# SCH_Proj_2026_2026-04-17.net
KiCad netlist of a schematic drawn in EasyEDA
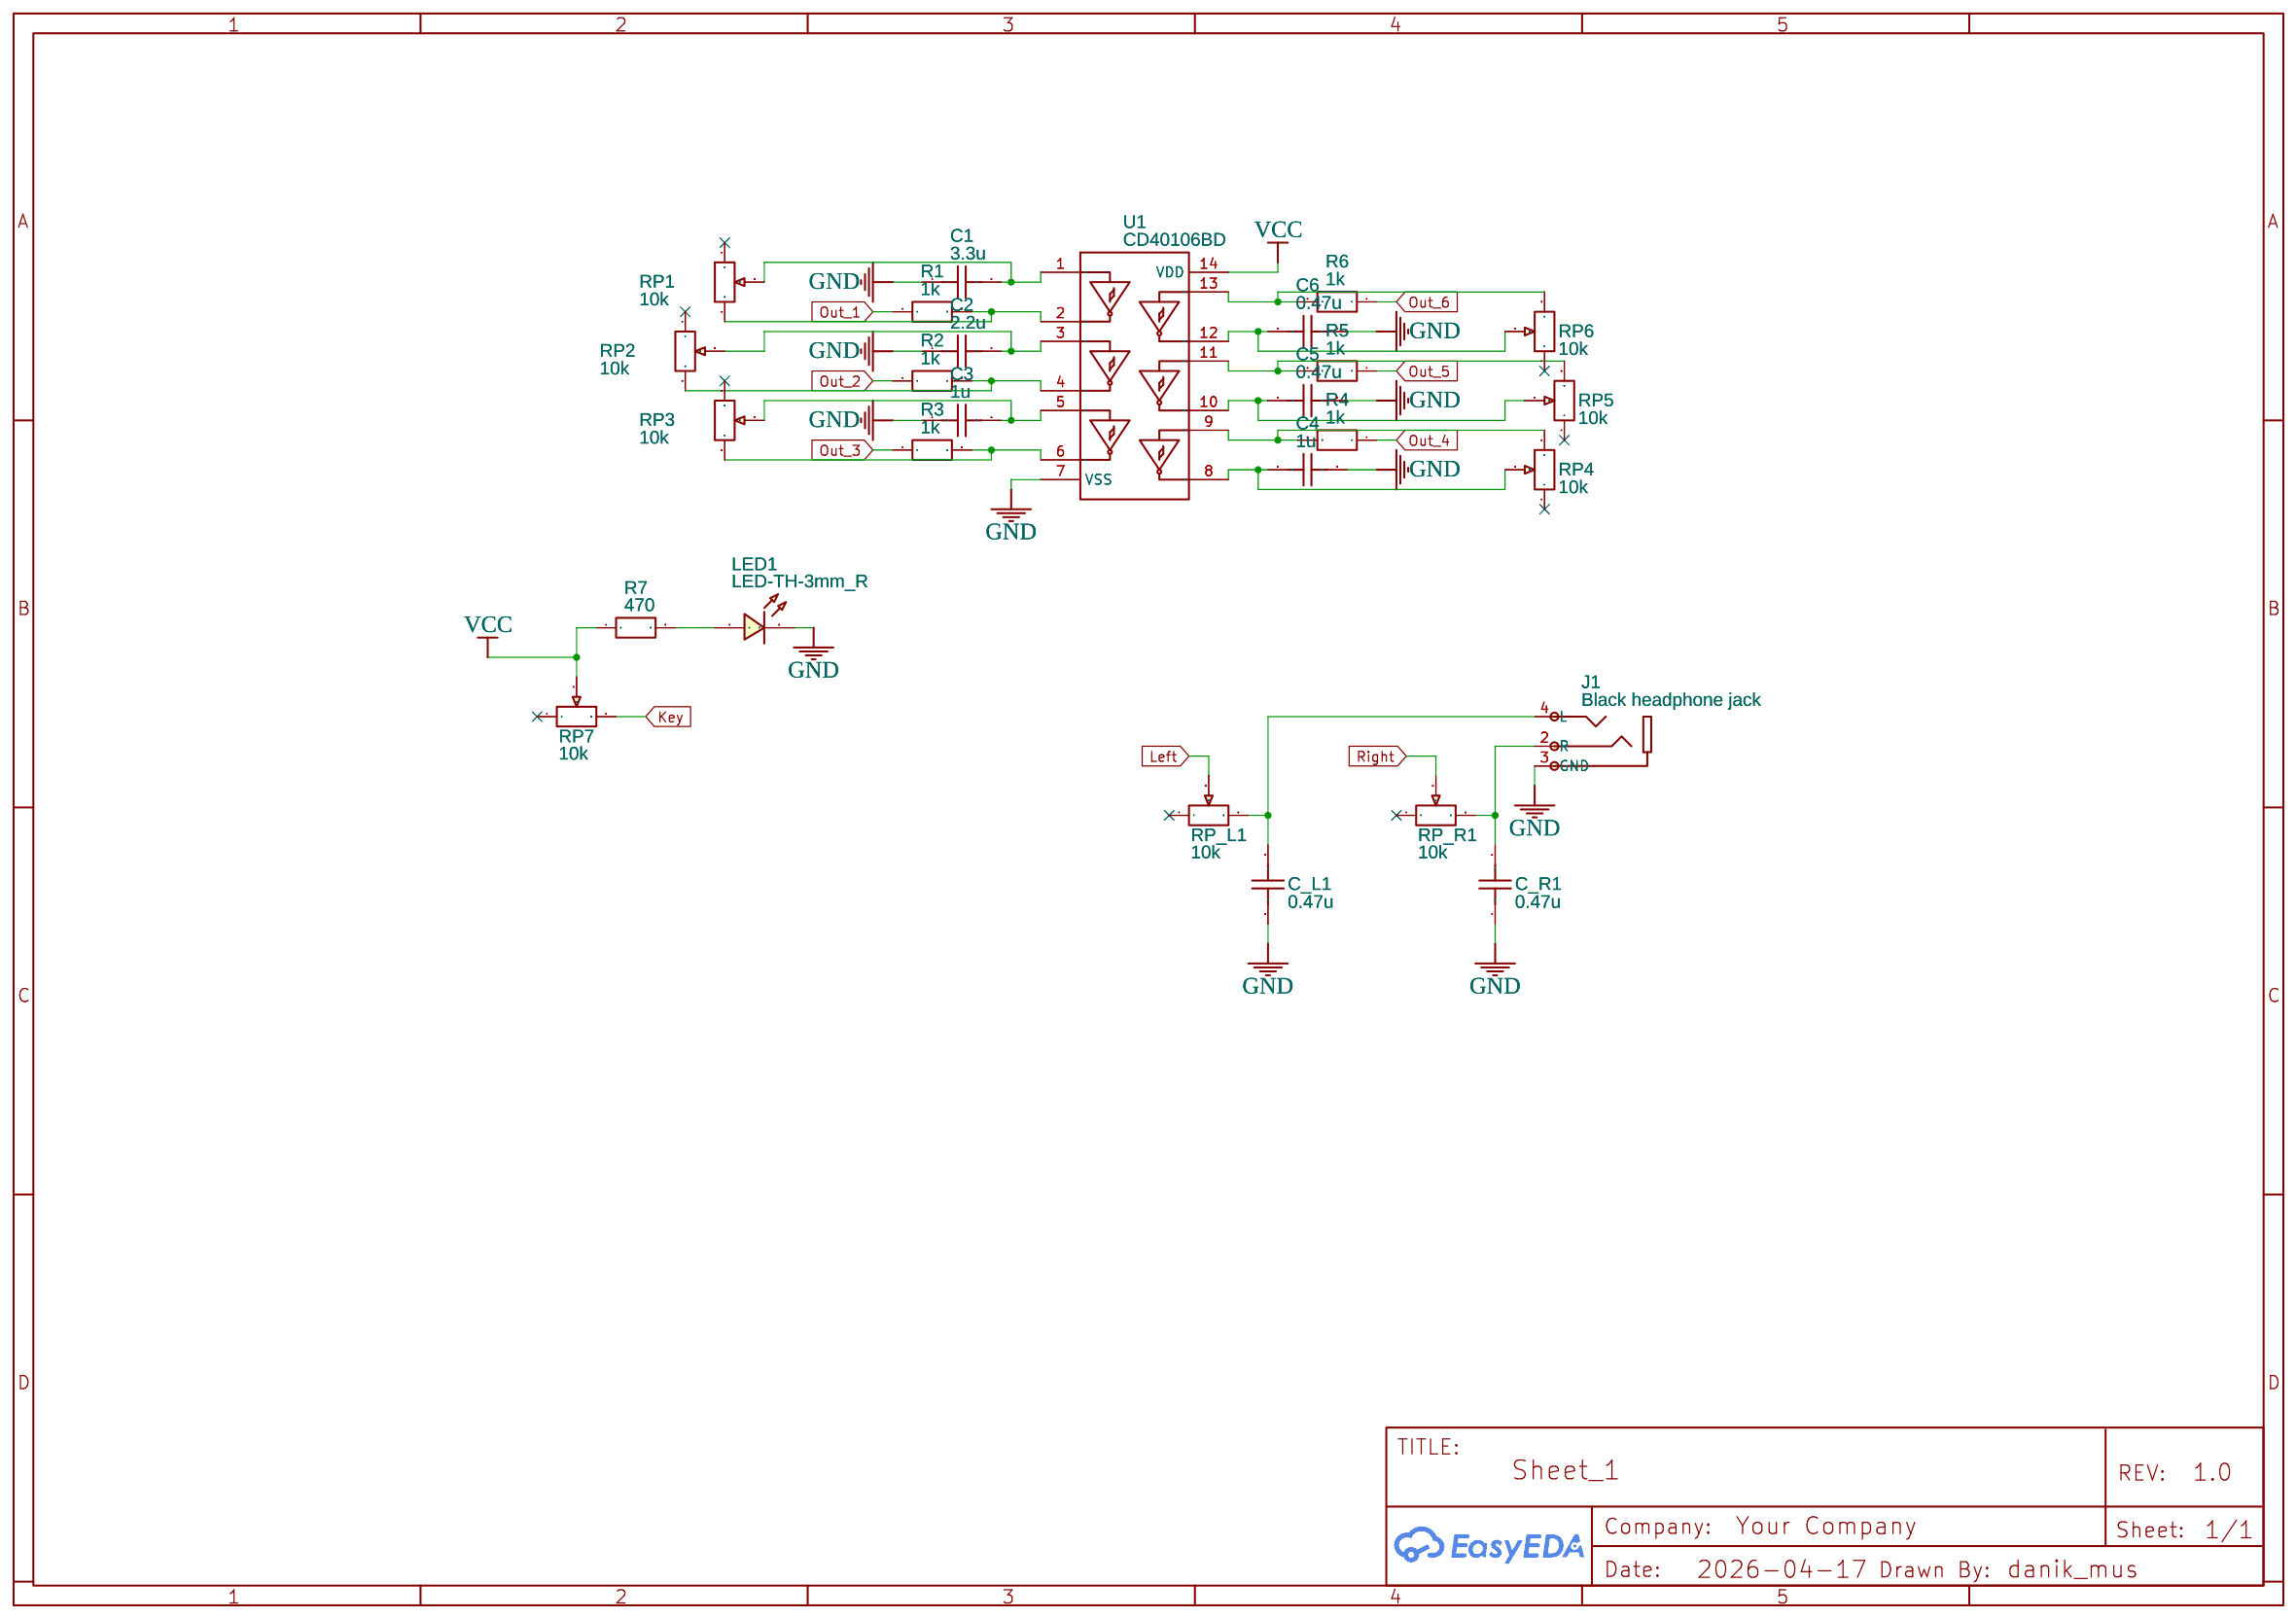
[diagram p0: schematic sheet]

(export (version "E")
  (design (tool "Eeschema 10.0.6"))
  (components
    (comp (ref "C1") (value "3.3u") (libsource (lib "") (part "C_0603_US_2")))
    (comp (ref "C2") (value "2.2u") (libsource (lib "") (part "C_0603_US_2")))
    (comp (ref "C3") (value "1u") (libsource (lib "") (part "C_0603_US_2")))
    (comp (ref "C4") (value "1u") (libsource (lib "") (part "C_0603_US")))
    (comp (ref "C5") (value "0.47u") (libsource (lib "") (part "C_0603_US")))
    (comp (ref "C6") (value "0.47u") (libsource (lib "") (part "C_0603_US")))
    (comp (ref "C_L1") (value "0.47u") (libsource (lib "") (part "C_0603_US_3")))
    (comp (ref "C_R1") (value "0.47u") (libsource (lib "") (part "C_0603_US_1")))
    (comp (ref "J1")
      (value "Black headphone jack")
      (fields (field (name "Manufacturer Part") "320B直插") (field (name "Manufacturer") "BOOMELE(博穆精密)"))
      (libsource (lib "") (part "Black headphone jack"))
    )
    (comp (ref "LED1")
      (value "LED-TH-3mm_R")
      (fields
        (field (name "Manufacturer Part") "204-10SDRD/S530-A3-L")
        (field (name "Manufacturer") "EVERLIGHT(台湾亿光)")
      )
      (libsource (lib "") (part "LED-TH-3mm_R"))
    )
    (comp (ref "R1") (value "1k") (libsource (lib "") (part "R_AXIAL-1.0_EU")))
    (comp (ref "R2") (value "1k") (libsource (lib "") (part "R_AXIAL-1.0_EU")))
    (comp (ref "R3") (value "1k") (libsource (lib "") (part "R_AXIAL-1.0_EU")))
    (comp (ref "R4") (value "1k") (libsource (lib "") (part "R_AXIAL-1.0_EU_1")))
    (comp (ref "R5") (value "1k") (libsource (lib "") (part "R_AXIAL-1.0_EU_1")))
    (comp (ref "R6") (value "1k") (libsource (lib "") (part "R_AXIAL-1.0_EU_1")))
    (comp (ref "R7") (value "470") (libsource (lib "") (part "R_AXIAL-1.0_EU")))
    (comp (ref "RP1") (value "10k") (libsource (lib "") (part "POTRES COPY COPY_2")))
    (comp (ref "RP2") (value "10k") (libsource (lib "") (part "POTRES COPY COPY_2")))
    (comp (ref "RP3") (value "10k") (libsource (lib "") (part "POTRES COPY COPY_2")))
    (comp (ref "RP4") (value "10k") (libsource (lib "") (part "POTRES COPY COPY_3")))
    (comp (ref "RP5") (value "10k") (libsource (lib "") (part "POTRES COPY COPY_3")))
    (comp (ref "RP6") (value "10k") (libsource (lib "") (part "POTRES COPY COPY_3")))
    (comp (ref "RP7") (value "10k") (libsource (lib "") (part "POTRES COPY COPY_4")))
    (comp (ref "RP_L1") (value "10k") (libsource (lib "") (part "POTRES COPY COPY_1")))
    (comp (ref "RP_R1") (value "10k") (libsource (lib "") (part "POTRES COPY COPY")))
    (comp (ref "U1")
      (value "CD40106BD")
      (fields (field (name "Manufacturer") "Sungine(双竞集成)"))
      (libsource (lib "") (part "CD40106BD"))
    )
  )
  (nets
    (net (code "1") (name "GND") (class "Default")
      (node (ref "C1") (pin "1") (pinfunction "1_1") (pintype "unspecified"))
      (node (ref "C2") (pin "1") (pinfunction "1_1") (pintype "unspecified"))
      (node (ref "C3") (pin "1") (pinfunction "1_1") (pintype "unspecified"))
      (node (ref "C4") (pin "1") (pinfunction "1_1") (pintype "unspecified"))
      (node (ref "C5") (pin "1") (pinfunction "1_1") (pintype "unspecified"))
      (node (ref "C6") (pin "1") (pinfunction "1_1") (pintype "unspecified"))
      (node (ref "C_L1") (pin "1") (pinfunction "1_1") (pintype "unspecified"))
      (node (ref "C_R1") (pin "1") (pinfunction "1_1") (pintype "unspecified"))
      (node (ref "J1") (pin "3") (pinfunction "GND_3") (pintype "input"))
      (node (ref "LED1") (pin "2") (pinfunction "2_2") (pintype "unspecified"))
      (node (ref "U1") (pin "7") (pinfunction "VSS_7") (pintype "unspecified"))
    )
    (net (code "2") (name "Key") (class "Default")
      (node (ref "RP7") (pin "3") (pinfunction "3_3") (pintype "input"))
    )
    (net (code "3") (name "Left") (class "Default")
      (node (ref "RP_L1") (pin "2") (pinfunction "2_2") (pintype "input"))
    )
    (net (code "4") (name "Net-(C1-Pad2)") (class "Default")
      (node (ref "C1") (pin "2") (pinfunction "2_2") (pintype "unspecified"))
      (node (ref "RP1") (pin "2") (pinfunction "2_2") (pintype "input"))
      (node (ref "U1") (pin "1") (pinfunction "1_1") (pintype "unspecified"))
    )
    (net (code "5") (name "Net-(C2-Pad2)") (class "Default")
      (node (ref "C2") (pin "2") (pinfunction "2_2") (pintype "unspecified"))
      (node (ref "RP2") (pin "2") (pinfunction "2_2") (pintype "input"))
      (node (ref "U1") (pin "3") (pinfunction "3_3") (pintype "unspecified"))
    )
    (net (code "6") (name "Net-(C3-Pad2)") (class "Default")
      (node (ref "C3") (pin "2") (pinfunction "2_2") (pintype "unspecified"))
      (node (ref "RP3") (pin "2") (pinfunction "2_2") (pintype "input"))
      (node (ref "U1") (pin "5") (pinfunction "5_5") (pintype "unspecified"))
    )
    (net (code "7") (name "Net-(C4-Pad2)") (class "Default")
      (node (ref "C4") (pin "2") (pinfunction "2_2") (pintype "unspecified"))
      (node (ref "RP4") (pin "2") (pinfunction "2_2") (pintype "input"))
      (node (ref "U1") (pin "8") (pinfunction "8_8") (pintype "unspecified"))
    )
    (net (code "8") (name "Net-(C5-Pad2)") (class "Default")
      (node (ref "C5") (pin "2") (pinfunction "2_2") (pintype "unspecified"))
      (node (ref "RP5") (pin "2") (pinfunction "2_2") (pintype "input"))
      (node (ref "U1") (pin "10") (pinfunction "10_10") (pintype "unspecified"))
    )
    (net (code "9") (name "Net-(C6-Pad2)") (class "Default")
      (node (ref "C6") (pin "2") (pinfunction "2_2") (pintype "unspecified"))
      (node (ref "RP6") (pin "2") (pinfunction "2_2") (pintype "input"))
      (node (ref "U1") (pin "12") (pinfunction "12_12") (pintype "unspecified"))
    )
    (net (code "10") (name "Net-(J1-L)") (class "Default")
      (node (ref "C_L1") (pin "2") (pinfunction "2_2") (pintype "unspecified"))
      (node (ref "J1") (pin "4") (pinfunction "L_4") (pintype "input"))
      (node (ref "RP_L1") (pin "3") (pinfunction "3_3") (pintype "input"))
    )
    (net (code "11") (name "Net-(J1-R)") (class "Default")
      (node (ref "C_R1") (pin "2") (pinfunction "2_2") (pintype "unspecified"))
      (node (ref "J1") (pin "2") (pinfunction "R_2") (pintype "input"))
      (node (ref "RP_R1") (pin "3") (pinfunction "3_3") (pintype "input"))
    )
    (net (code "12") (name "Net-(LED1-Pad1)") (class "Default")
      (node (ref "LED1") (pin "1") (pinfunction "1_1") (pintype "unspecified"))
      (node (ref "R7") (pin "2") (pinfunction "2_2") (pintype "unspecified"))
    )
    (net (code "13") (name "Net-(R1-Pad2)") (class "Default")
      (node (ref "R1") (pin "2") (pinfunction "2_2") (pintype "unspecified"))
      (node (ref "RP1") (pin "3") (pinfunction "3_3") (pintype "input"))
      (node (ref "U1") (pin "2") (pinfunction "2_2") (pintype "unspecified"))
    )
    (net (code "14") (name "Net-(R2-Pad2)") (class "Default")
      (node (ref "R2") (pin "2") (pinfunction "2_2") (pintype "unspecified"))
      (node (ref "RP2") (pin "3") (pinfunction "3_3") (pintype "input"))
      (node (ref "U1") (pin "4") (pinfunction "4_4") (pintype "unspecified"))
    )
    (net (code "15") (name "Net-(R3-Pad2)") (class "Default")
      (node (ref "R3") (pin "2") (pinfunction "2_2") (pintype "unspecified"))
      (node (ref "RP3") (pin "3") (pinfunction "3_3") (pintype "input"))
      (node (ref "U1") (pin "6") (pinfunction "6_6") (pintype "unspecified"))
    )
    (net (code "16") (name "Net-(R4-Pad2)") (class "Default")
      (node (ref "R4") (pin "2") (pinfunction "2_2") (pintype "unspecified"))
      (node (ref "RP4") (pin "3") (pinfunction "3_3") (pintype "input"))
      (node (ref "U1") (pin "9") (pinfunction "9_9") (pintype "unspecified"))
    )
    (net (code "17") (name "Net-(R5-Pad2)") (class "Default")
      (node (ref "R5") (pin "2") (pinfunction "2_2") (pintype "unspecified"))
      (node (ref "RP5") (pin "3") (pinfunction "3_3") (pintype "input"))
      (node (ref "U1") (pin "11") (pinfunction "11_11") (pintype "unspecified"))
    )
    (net (code "18") (name "Net-(R6-Pad2)") (class "Default")
      (node (ref "R6") (pin "2") (pinfunction "2_2") (pintype "unspecified"))
      (node (ref "RP6") (pin "3") (pinfunction "3_3") (pintype "input"))
      (node (ref "U1") (pin "13") (pinfunction "13_13") (pintype "unspecified"))
    )
    (net (code "19") (name "Out_1") (class "Default")
      (node (ref "R1") (pin "1") (pinfunction "1_1") (pintype "unspecified"))
    )
    (net (code "20") (name "Out_2") (class "Default")
      (node (ref "R2") (pin "1") (pinfunction "1_1") (pintype "unspecified"))
    )
    (net (code "21") (name "Out_3") (class "Default")
      (node (ref "R3") (pin "1") (pinfunction "1_1") (pintype "unspecified"))
    )
    (net (code "22") (name "Out_4") (class "Default")
      (node (ref "R4") (pin "1") (pinfunction "1_1") (pintype "unspecified"))
    )
    (net (code "23") (name "Out_5") (class "Default")
      (node (ref "R5") (pin "1") (pinfunction "1_1") (pintype "unspecified"))
    )
    (net (code "24") (name "Out_6") (class "Default")
      (node (ref "R6") (pin "1") (pinfunction "1_1") (pintype "unspecified"))
    )
    (net (code "25") (name "Right") (class "Default")
      (node (ref "RP_R1") (pin "2") (pinfunction "2_2") (pintype "input"))
    )
    (net (code "26") (name "VCC") (class "Default")
      (node (ref "R7") (pin "1") (pinfunction "1_1") (pintype "unspecified"))
      (node (ref "RP7") (pin "2") (pinfunction "2_2") (pintype "input"))
      (node (ref "U1") (pin "14") (pinfunction "VDD_14") (pintype "unspecified"))
    )
    (net (code "27") (name "unconnected-(RP1-Pad1)") (class "Default")
      (node (ref "RP1") (pin "1") (pinfunction "1_1") (pintype "input+no_connect"))
    )
    (net (code "28") (name "unconnected-(RP2-Pad1)") (class "Default")
      (node (ref "RP2") (pin "1") (pinfunction "1_1") (pintype "input+no_connect"))
    )
    (net (code "29") (name "unconnected-(RP3-Pad1)") (class "Default")
      (node (ref "RP3") (pin "1") (pinfunction "1_1") (pintype "input+no_connect"))
    )
    (net (code "30") (name "unconnected-(RP4-Pad1)") (class "Default")
      (node (ref "RP4") (pin "1") (pinfunction "1_1") (pintype "input+no_connect"))
    )
    (net (code "31") (name "unconnected-(RP5-Pad1)") (class "Default")
      (node (ref "RP5") (pin "1") (pinfunction "1_1") (pintype "input+no_connect"))
    )
    (net (code "32") (name "unconnected-(RP6-Pad1)") (class "Default")
      (node (ref "RP6") (pin "1") (pinfunction "1_1") (pintype "input+no_connect"))
    )
    (net (code "33") (name "unconnected-(RP7-Pad1)") (class "Default")
      (node (ref "RP7") (pin "1") (pinfunction "1_1") (pintype "input+no_connect"))
    )
    (net (code "34") (name "unconnected-(RP_L1-Pad1)") (class "Default")
      (node (ref "RP_L1") (pin "1") (pinfunction "1_1") (pintype "input+no_connect"))
    )
    (net (code "35") (name "unconnected-(RP_R1-Pad1)") (class "Default")
      (node (ref "RP_R1") (pin "1") (pinfunction "1_1") (pintype "input+no_connect"))
    )
  )
)
